# Grove_-_Temperature_Humidity_Sensor_High.net
KiCad netlist of a schematic drawn in EAGLE
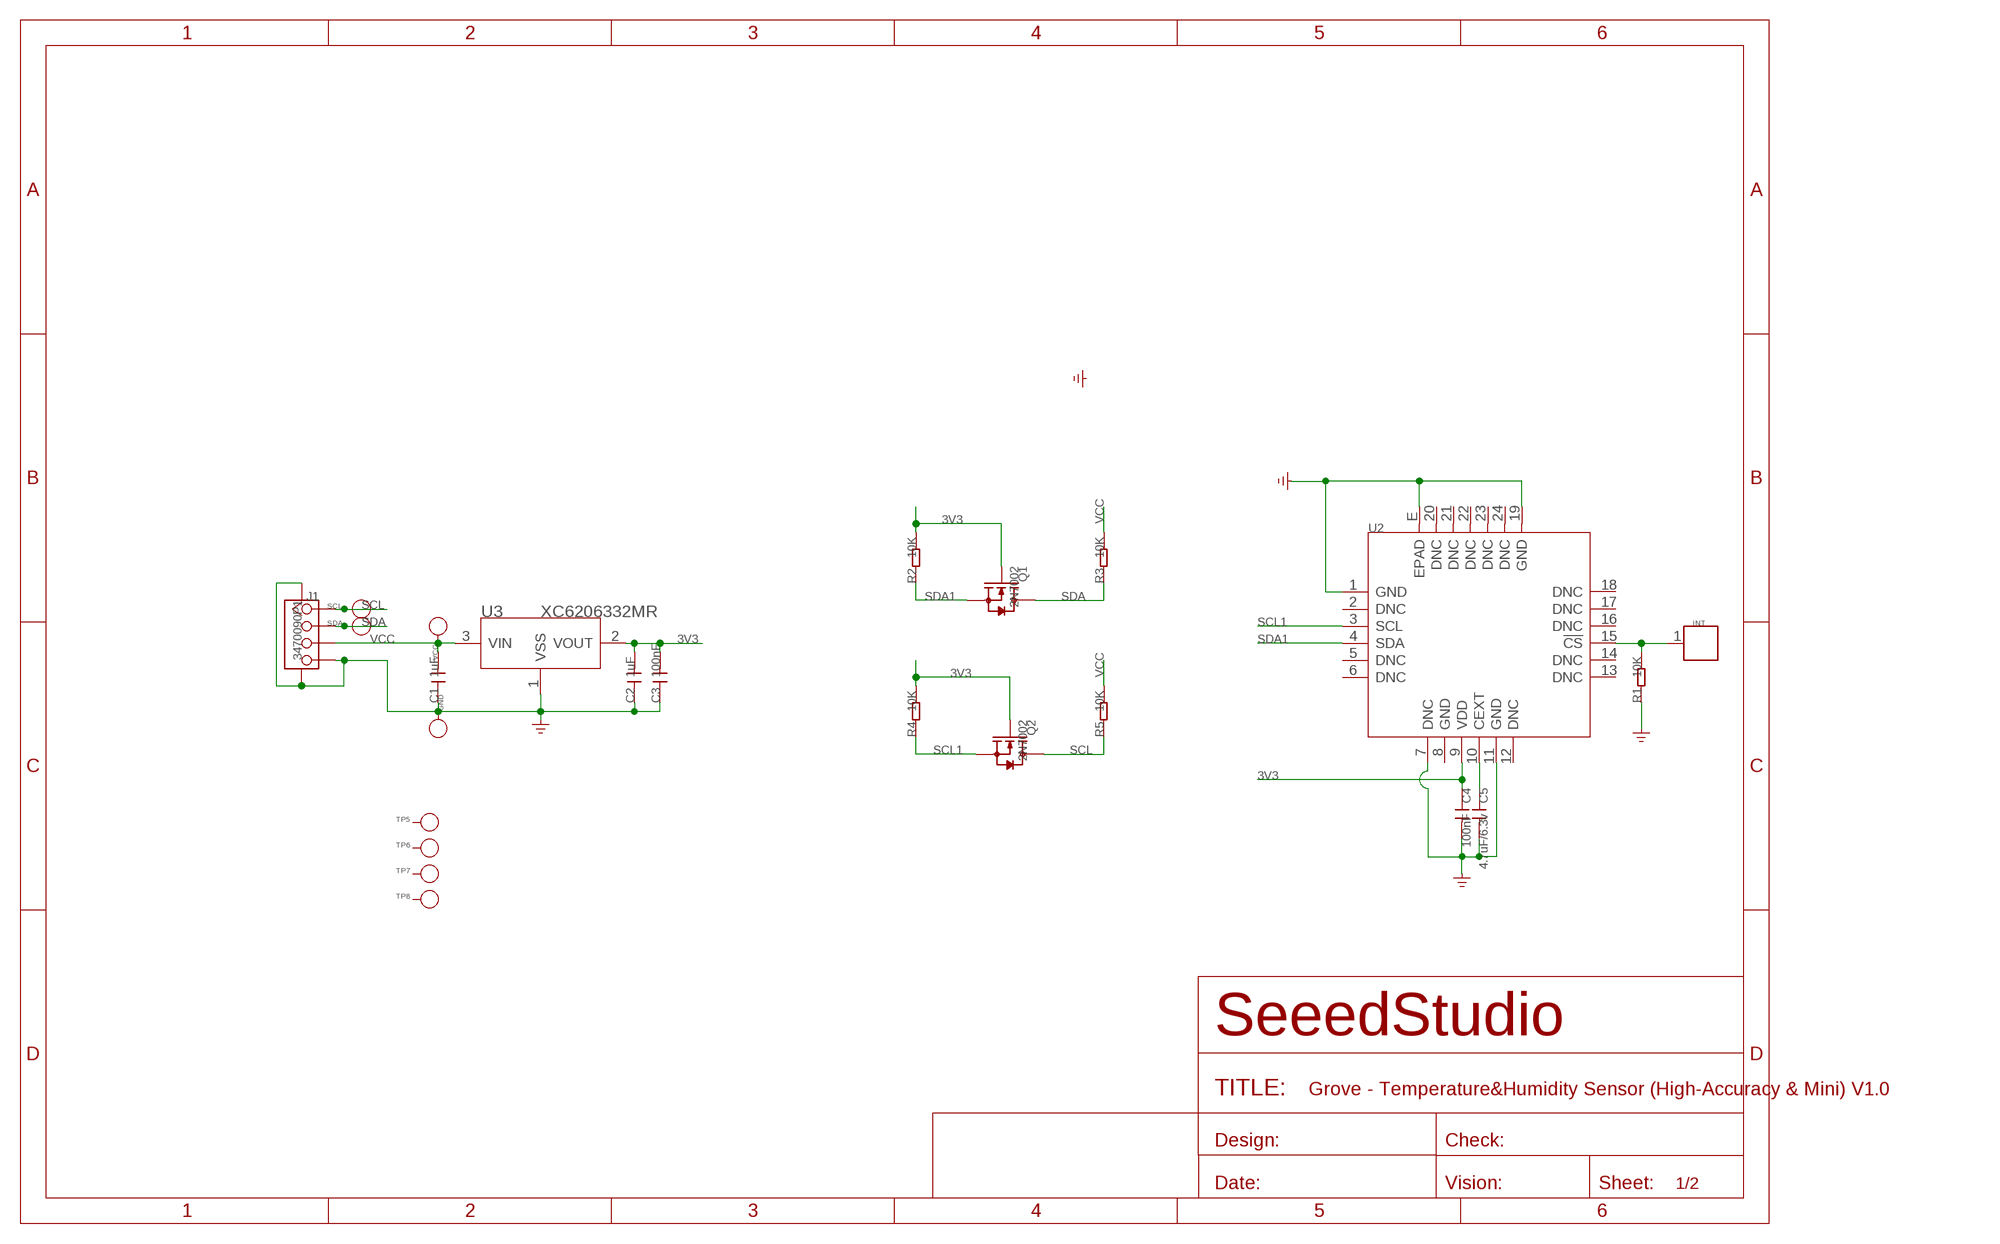
[diagram p0: schematic, sheet 1]
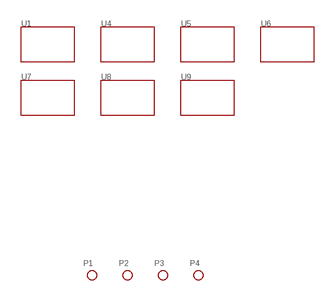
[diagram p1: schematic, sheet 2]

(export (version "E")
  (design (tool "Eeschema 10.0.6"))
  (components
    (comp (ref "P1")
      (value "PAD-MARK")
      (footprint "eagle-import:ROUND-MARK-1.0")
      (fields (field (name "PARTNO") "DNP"))
      (libsource (lib "eagle-import") (part "PAD-MARK"))
    )
    (comp (ref "P2")
      (value "PAD-MARK")
      (footprint "eagle-import:ROUND-MARK-1.0")
      (fields (field (name "PARTNO") "DNP"))
      (libsource (lib "eagle-import") (part "PAD-MARK"))
    )
    (comp (ref "P3")
      (value "PAD-MARK")
      (footprint "eagle-import:ROUND-MARK-1.0")
      (fields (field (name "PARTNO") "DNP"))
      (libsource (lib "eagle-import") (part "PAD-MARK"))
    )
    (comp (ref "P4")
      (value "PAD-MARK")
      (footprint "eagle-import:ROUND-MARK-1.0")
      (fields (field (name "PARTNO") "DNP"))
      (libsource (lib "eagle-import") (part "PAD-MARK"))
    )
    (comp (ref "U1")
      (value "TWIG'2U'")
      (footprint "eagle-import:GROVE-TEST-PLATFORM")
      (libsource (lib "eagle-import") (part "TWIG'2U'"))
    )
    (comp (ref "U4")
      (value "TWIG'2U'")
      (footprint "eagle-import:GROVE-TEST-PLATFORM")
      (libsource (lib "eagle-import") (part "TWIG'2U'"))
    )
    (comp (ref "U5")
      (value "TWIG'2U'")
      (footprint "eagle-import:GROVE-TEST-PLATFORM")
      (libsource (lib "eagle-import") (part "TWIG'2U'"))
    )
    (comp (ref "U6")
      (value "TWIG'2U'")
      (footprint "eagle-import:GROVE-TEST-PLATFORM")
      (libsource (lib "eagle-import") (part "TWIG'2U'"))
    )
    (comp (ref "U7")
      (value "TWIG'2U'")
      (footprint "eagle-import:GROVE-TEST-PLATFORM")
      (libsource (lib "eagle-import") (part "TWIG'2U'"))
    )
    (comp (ref "U8")
      (value "TWIG'2U'")
      (footprint "eagle-import:GROVE-TEST-PLATFORM")
      (libsource (lib "eagle-import") (part "TWIG'2U'"))
    )
    (comp (ref "U9")
      (value "TWIG'2U'")
      (footprint "eagle-import:GROVE-TEST-PLATFORM")
      (libsource (lib "eagle-import") (part "TWIG'2U'"))
    )
    (comp (ref "C1")
      (value "1uF")
      (footprint "eagle-import:C0603")
      (libsource (lib "eagle-import") (part "C-0603"))
    )
    (comp (ref "C2")
      (value "1uF")
      (footprint "eagle-import:C0603")
      (libsource (lib "eagle-import") (part "C-0603"))
    )
    (comp (ref "C3")
      (value "100nF")
      (footprint "eagle-import:C0603")
      (libsource (lib "eagle-import") (part "C-0603"))
    )
    (comp (ref "C4")
      (value "100nF")
      (footprint "eagle-import:C0603")
      (libsource (lib "eagle-import") (part "C-0603"))
    )
    (comp (ref "C5")
      (value "4.7uF/6.3v")
      (footprint "eagle-import:C0603")
      (libsource (lib "eagle-import") (part "C-0603"))
    )
    (comp (ref "GND")
      (value "PAD-TEST-POINT'4545'")
      (footprint "eagle-import:TP_4545")
      (fields (field (name "PARTNO") "DNP"))
      (libsource (lib "eagle-import") (part "PAD-TEST-POINT'4545'"))
    )
    (comp (ref "INT")
      (value "PAD'60/30'")
      (footprint "eagle-import:1P-65_35MIL")
      (libsource (lib "eagle-import") (part "PAD'60/30'"))
    )
    (comp (ref "J1")
      (value "3470090P1")
      (footprint "eagle-import:4P-SMD-2.0")
      (libsource (lib "eagle-import") (part "TWIG-4P-2.0-SMD-FEMALE-REINFORCE'DD'"))
    )
    (comp (ref "Q1")
      (value "2N7002")
      (footprint "eagle-import:SOT23")
      (libsource (lib "eagle-import") (part "MOSFET-N'SOT23'"))
    )
    (comp (ref "Q2")
      (value "2N7002")
      (footprint "eagle-import:SOT23")
      (libsource (lib "eagle-import") (part "MOSFET-N'SOT23'"))
    )
    (comp (ref "R1")
      (value "10K")
      (footprint "eagle-import:R0603")
      (libsource (lib "eagle-import") (part "R-0603"))
    )
    (comp (ref "R2")
      (value "10K")
      (footprint "eagle-import:R0603")
      (libsource (lib "eagle-import") (part "R-0603"))
    )
    (comp (ref "R3")
      (value "10K")
      (footprint "eagle-import:R0603")
      (libsource (lib "eagle-import") (part "R-0603"))
    )
    (comp (ref "R4")
      (value "10K")
      (footprint "eagle-import:R0603")
      (libsource (lib "eagle-import") (part "R-0603"))
    )
    (comp (ref "R5")
      (value "10K")
      (footprint "eagle-import:R0603")
      (libsource (lib "eagle-import") (part "R-0603"))
    )
    (comp (ref "SCL")
      (value "PAD-TEST-POINT'4545'")
      (footprint "eagle-import:TP_4545")
      (fields (field (name "PARTNO") "DNP"))
      (libsource (lib "eagle-import") (part "PAD-TEST-POINT'4545'"))
    )
    (comp (ref "SDA")
      (value "PAD-TEST-POINT'4545'")
      (footprint "eagle-import:TP_4545")
      (fields (field (name "PARTNO") "DNP"))
      (libsource (lib "eagle-import") (part "PAD-TEST-POINT'4545'"))
    )
    (comp (ref "TP5")
      (value "PAD-TEST-POINT'4545'")
      (footprint "eagle-import:TP_4545")
      (fields (field (name "PARTNO") "DNP"))
      (libsource (lib "eagle-import") (part "PAD-TEST-POINT'4545'"))
    )
    (comp (ref "TP6")
      (value "PAD-TEST-POINT'4545'")
      (footprint "eagle-import:TP_4545")
      (fields (field (name "PARTNO") "DNP"))
      (libsource (lib "eagle-import") (part "PAD-TEST-POINT'4545'"))
    )
    (comp (ref "TP7")
      (value "PAD-TEST-POINT'4545'")
      (footprint "eagle-import:TP_4545")
      (fields (field (name "PARTNO") "DNP"))
      (libsource (lib "eagle-import") (part "PAD-TEST-POINT'4545'"))
    )
    (comp (ref "TP8")
      (value "PAD-TEST-POINT'4545'")
      (footprint "eagle-import:TP_4545")
      (fields (field (name "PARTNO") "DNP"))
      (libsource (lib "eagle-import") (part "PAD-TEST-POINT'4545'"))
    )
    (comp (ref "U2")
      (value "SENSOR-TH02")
      (footprint "eagle-import:QFN24")
      (libsource (lib "eagle-import") (part "SENSOR-TH02"))
    )
    (comp (ref "U3")
      (value "XC6206332MR")
      (footprint "eagle-import:SOT23")
      (libsource (lib "eagle-import") (part "XC6206MR"))
    )
    (comp (ref "VCC")
      (value "PAD-TEST-POINT'4545'")
      (footprint "eagle-import:TP_4545")
      (fields (field (name "PARTNO") "DNP"))
      (libsource (lib "eagle-import") (part "PAD-TEST-POINT'4545'"))
    )
  )
  (nets
    (net (code "1") (name "3V3") (class "Default")
      (node (ref "C2") (pin "2") (pinfunction "2_2") (pintype "passive"))
      (node (ref "C3") (pin "2") (pinfunction "2_2") (pintype "passive"))
      (node (ref "C4") (pin "1") (pinfunction "1_1") (pintype "passive"))
      (node (ref "Q1") (pin "1") (pinfunction "G_1") (pintype "passive"))
      (node (ref "Q2") (pin "1") (pinfunction "G_1") (pintype "passive"))
      (node (ref "R2") (pin "2") (pinfunction "2_2") (pintype "passive"))
      (node (ref "R4") (pin "2") (pinfunction "2_2") (pintype "passive"))
      (node (ref "U2") (pin "9") (pinfunction "VDD_9") (pintype "bidirectional"))
      (node (ref "U3") (pin "2") (pinfunction "VOUT_2") (pintype "output"))
    )
    (net (code "2") (name "GND") (class "Default")
      (node (ref "C1") (pin "1") (pinfunction "1_1") (pintype "passive"))
      (node (ref "C2") (pin "1") (pinfunction "1_1") (pintype "passive"))
      (node (ref "C3") (pin "1") (pinfunction "1_1") (pintype "passive"))
      (node (ref "C4") (pin "2") (pinfunction "2_2") (pintype "passive"))
      (node (ref "C5") (pin "2") (pinfunction "2_2") (pintype "passive"))
      (node (ref "GND") (pin "T") (pinfunction "T_T") (pintype "bidirectional"))
      (node (ref "J1") (pin "4") (pinfunction "4_4") (pintype "bidirectional"))
      (node (ref "J1") (pin "SS1") (pinfunction "SS1_SS1") (pintype "bidirectional"))
      (node (ref "J1") (pin "SS2") (pinfunction "SS2_SS2") (pintype "bidirectional"))
      (node (ref "R1") (pin "1") (pinfunction "1_1") (pintype "passive"))
      (node (ref "U2") (pin "1") (pinfunction "GND_1") (pintype "bidirectional"))
      (node (ref "U2") (pin "11") (pinfunction "GND_11") (pintype "bidirectional"))
      (node (ref "U2") (pin "19") (pinfunction "GND_19") (pintype "bidirectional"))
      (node (ref "U2") (pin "7") (pinfunction "DNC_7") (pintype "bidirectional"))
      (node (ref "U2") (pin "E") (pinfunction "EPAD_E") (pintype "bidirectional"))
      (node (ref "U3") (pin "1") (pinfunction "VSS_1") (pintype "power_in"))
    )
    (net (code "3") (name "Net-(INT-P$1)") (class "Default")
      (node (ref "INT") (pin "1") (pinfunction "P$1_1") (pintype "bidirectional"))
      (node (ref "R1") (pin "2") (pinfunction "2_2") (pintype "passive"))
      (node (ref "U2") (pin "15") (pinfunction "~{CS}_15") (pintype "bidirectional"))
    )
    (net (code "4") (name "Net-(U2-CEXT)") (class "Default")
      (node (ref "C5") (pin "1") (pinfunction "1_1") (pintype "passive"))
      (node (ref "U2") (pin "10") (pinfunction "CEXT_10") (pintype "bidirectional"))
    )
    (net (code "5") (name "SCL") (class "Default")
      (node (ref "J1") (pin "1") (pinfunction "1_1") (pintype "bidirectional"))
      (node (ref "Q2") (pin "3") (pinfunction "D_3") (pintype "passive"))
      (node (ref "R5") (pin "1") (pinfunction "1_1") (pintype "passive"))
      (node (ref "SCL") (pin "T") (pinfunction "T_T") (pintype "bidirectional"))
    )
    (net (code "6") (name "SCL1") (class "Default")
      (node (ref "Q2") (pin "2") (pinfunction "S_2") (pintype "passive"))
      (node (ref "R4") (pin "1") (pinfunction "1_1") (pintype "passive"))
      (node (ref "U2") (pin "3") (pinfunction "SCL_3") (pintype "bidirectional"))
    )
    (net (code "7") (name "SDA") (class "Default")
      (node (ref "J1") (pin "2") (pinfunction "2_2") (pintype "bidirectional"))
      (node (ref "Q1") (pin "3") (pinfunction "D_3") (pintype "passive"))
      (node (ref "R3") (pin "1") (pinfunction "1_1") (pintype "passive"))
      (node (ref "SDA") (pin "T") (pinfunction "T_T") (pintype "bidirectional"))
    )
    (net (code "8") (name "SDA1") (class "Default")
      (node (ref "Q1") (pin "2") (pinfunction "S_2") (pintype "passive"))
      (node (ref "R2") (pin "1") (pinfunction "1_1") (pintype "passive"))
      (node (ref "U2") (pin "4") (pinfunction "SDA_4") (pintype "bidirectional"))
    )
    (net (code "9") (name "VCC") (class "Default")
      (node (ref "C1") (pin "2") (pinfunction "2_2") (pintype "passive"))
      (node (ref "J1") (pin "3") (pinfunction "3_3") (pintype "bidirectional"))
      (node (ref "R3") (pin "2") (pinfunction "2_2") (pintype "passive"))
      (node (ref "R5") (pin "2") (pinfunction "2_2") (pintype "passive"))
      (node (ref "U3") (pin "3") (pinfunction "VIN_3") (pintype "input"))
      (node (ref "VCC") (pin "T") (pinfunction "T_T") (pintype "bidirectional"))
    )
    (net (code "10") (name "unconnected-(TP5-PadT)") (class "Default")
      (node (ref "TP5") (pin "T") (pinfunction "T_T") (pintype "bidirectional"))
    )
    (net (code "11") (name "unconnected-(TP6-PadT)") (class "Default")
      (node (ref "TP6") (pin "T") (pinfunction "T_T") (pintype "bidirectional"))
    )
    (net (code "12") (name "unconnected-(TP7-PadT)") (class "Default")
      (node (ref "TP7") (pin "T") (pinfunction "T_T") (pintype "bidirectional"))
    )
    (net (code "13") (name "unconnected-(TP8-PadT)") (class "Default")
      (node (ref "TP8") (pin "T") (pinfunction "T_T") (pintype "bidirectional"))
    )
    (net (code "14") (name "unconnected-(U2-DNC-Pad2)") (class "Default")
      (node (ref "U2") (pin "2") (pinfunction "DNC_2") (pintype "bidirectional"))
    )
    (net (code "15") (name "unconnected-(U2-DNC-Pad5)") (class "Default")
      (node (ref "U2") (pin "5") (pinfunction "DNC_5") (pintype "bidirectional"))
    )
    (net (code "16") (name "unconnected-(U2-DNC-Pad6)") (class "Default")
      (node (ref "U2") (pin "6") (pinfunction "DNC_6") (pintype "bidirectional"))
    )
    (net (code "17") (name "unconnected-(U2-DNC-Pad12)") (class "Default")
      (node (ref "U2") (pin "12") (pinfunction "DNC_12") (pintype "bidirectional"))
    )
    (net (code "18") (name "unconnected-(U2-DNC-Pad13)") (class "Default")
      (node (ref "U2") (pin "13") (pinfunction "DNC_13") (pintype "bidirectional"))
    )
    (net (code "19") (name "unconnected-(U2-DNC-Pad14)") (class "Default")
      (node (ref "U2") (pin "14") (pinfunction "DNC_14") (pintype "bidirectional"))
    )
    (net (code "20") (name "unconnected-(U2-DNC-Pad16)") (class "Default")
      (node (ref "U2") (pin "16") (pinfunction "DNC_16") (pintype "bidirectional"))
    )
    (net (code "21") (name "unconnected-(U2-DNC-Pad17)") (class "Default")
      (node (ref "U2") (pin "17") (pinfunction "DNC_17") (pintype "bidirectional"))
    )
    (net (code "22") (name "unconnected-(U2-DNC-Pad18)") (class "Default")
      (node (ref "U2") (pin "18") (pinfunction "DNC_18") (pintype "bidirectional"))
    )
    (net (code "23") (name "unconnected-(U2-DNC-Pad20)") (class "Default")
      (node (ref "U2") (pin "20") (pinfunction "DNC_20") (pintype "bidirectional"))
    )
    (net (code "24") (name "unconnected-(U2-DNC-Pad21)") (class "Default")
      (node (ref "U2") (pin "21") (pinfunction "DNC_21") (pintype "bidirectional"))
    )
    (net (code "25") (name "unconnected-(U2-DNC-Pad22)") (class "Default")
      (node (ref "U2") (pin "22") (pinfunction "DNC_22") (pintype "bidirectional"))
    )
    (net (code "26") (name "unconnected-(U2-DNC-Pad23)") (class "Default")
      (node (ref "U2") (pin "23") (pinfunction "DNC_23") (pintype "bidirectional"))
    )
    (net (code "27") (name "unconnected-(U2-DNC-Pad24)") (class "Default")
      (node (ref "U2") (pin "24") (pinfunction "DNC_24") (pintype "bidirectional"))
    )
    (net (code "28") (name "unconnected-(U2-GND-Pad8)") (class "Default")
      (node (ref "U2") (pin "8") (pinfunction "GND_8") (pintype "bidirectional"))
    )
  )
)
